# m20048_GPS.net
KiCad netlist of a schematic drawn in Altium Designer
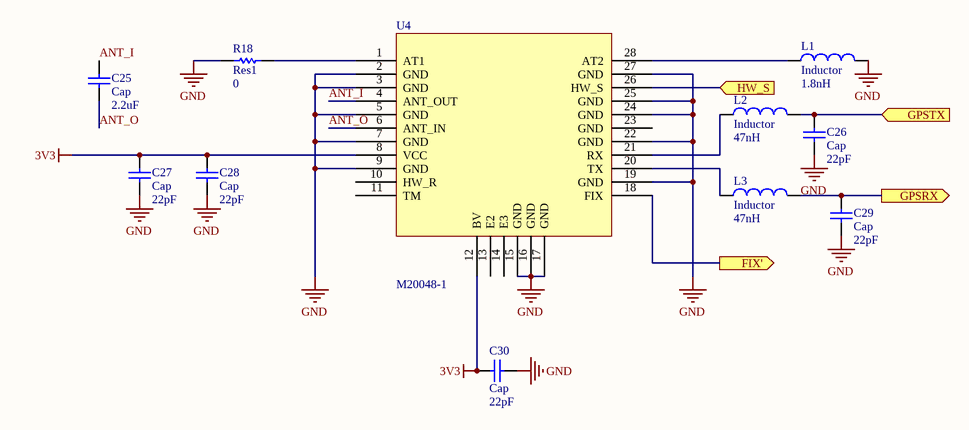
[diagram p0: m20048 GPS.SchDoc]

(export (version "E")
  (design (tool "Eeschema 10.0.6"))
  (components
    (comp (ref "C25")
      (value "Cap")
      (footprint "1608[0603]")
      (description "Capacitor")
      (fields (field (name "ALTIUM_VALUE") "2.2uF") (field (name "PUBLISHER") "Altium Limited"))
      (libsource (lib "Miscellaneous Devices") (part "Cap"))
    )
    (comp (ref "C26")
      (value "Cap")
      (footprint "0402-A")
      (description "Capacitor")
      (fields (field (name "ALTIUM_VALUE") "22pF") (field (name "PUBLISHER") "Altium Limited"))
      (libsource (lib "Miscellaneous Devices") (part "Cap"))
    )
    (comp (ref "C27")
      (value "Cap")
      (footprint "0402-A")
      (description "Capacitor")
      (fields (field (name "ALTIUM_VALUE") "22pF") (field (name "PUBLISHER") "Altium Limited"))
      (libsource (lib "Miscellaneous Devices") (part "Cap"))
    )
    (comp (ref "C28")
      (value "Cap")
      (footprint "0402-A")
      (description "Capacitor")
      (fields (field (name "ALTIUM_VALUE") "22pF") (field (name "PUBLISHER") "Altium Limited"))
      (libsource (lib "Miscellaneous Devices") (part "Cap"))
    )
    (comp (ref "C29")
      (value "Cap")
      (footprint "0402-A")
      (description "Capacitor")
      (fields (field (name "ALTIUM_VALUE") "22pF") (field (name "PUBLISHER") "Altium Limited"))
      (libsource (lib "Miscellaneous Devices") (part "Cap"))
    )
    (comp (ref "C30")
      (value "Cap")
      (footprint "0402-A")
      (description "Capacitor")
      (fields (field (name "ALTIUM_VALUE") "22pF") (field (name "PUBLISHER") "Altium Limited"))
      (libsource (lib "Miscellaneous Devices") (part "Cap"))
    )
    (comp (ref "L1")
      (value "Inductor")
      (footprint "0402-A")
      (fields (field (name "ALTIUM_VALUE") "1.8nH") (field (name "PUBLISHER") "Altium Limited"))
      (libsource (lib "Miscellaneous Devices") (part "Inductor"))
    )
    (comp (ref "L2")
      (value "Inductor")
      (footprint "0402-A")
      (fields (field (name "ALTIUM_VALUE") "47nH") (field (name "PUBLISHER") "Altium Limited"))
      (libsource (lib "Miscellaneous Devices") (part "Inductor"))
    )
    (comp (ref "L3")
      (value "Inductor")
      (footprint "0402-A")
      (fields (field (name "ALTIUM_VALUE") "47nH") (field (name "PUBLISHER") "Altium Limited"))
      (libsource (lib "Miscellaneous Devices") (part "Inductor"))
    )
    (comp (ref "R18")
      (value "Res1")
      (footprint "0402-A")
      (description "Resistor")
      (fields (field (name "ALTIUM_VALUE") "0") (field (name "PUBLISHER") "Altium Limited"))
      (libsource (lib "Miscellaneous Devices") (part "Res1"))
    )
    (comp (ref "U4") (value "M20048-1") (footprint "M20048-1") (libsource (lib "m20048") (part "M20048-1")))
  )
  (nets
    (net (code "1") (name "/ANT_I") (class "Default")
      (node (ref "C25") (pin "2") (pinfunction "2_2") (pintype "passive"))
      (node (ref "U4") (pin "4") (pinfunction "ANT_OUT_4") (pintype "passive"))
    )
    (net (code "2") (name "/ANT_O") (class "Default")
      (node (ref "C25") (pin "1") (pinfunction "1_1") (pintype "passive"))
      (node (ref "U4") (pin "6") (pinfunction "ANT_IN_6") (pintype "passive"))
    )
    (net (code "3") (name "/FIX'") (class "Default")
      (node (ref "U4") (pin "18") (pinfunction "FIX_18") (pintype "passive"))
    )
    (net (code "4") (name "/GPSRX") (class "Default")
      (node (ref "C29") (pin "2") (pinfunction "2_2") (pintype "passive"))
      (node (ref "L3") (pin "2") (pinfunction "2_2") (pintype "passive"))
    )
    (net (code "5") (name "/GPSTX") (class "Default")
      (node (ref "C26") (pin "2") (pinfunction "2_2") (pintype "passive"))
      (node (ref "L2") (pin "2") (pinfunction "2_2") (pintype "passive"))
    )
    (net (code "6") (name "/HW_S") (class "Default")
      (node (ref "U4") (pin "26") (pinfunction "HW_S_26") (pintype "passive"))
    )
    (net (code "7") (name "3V3") (class "Default")
      (node (ref "C27") (pin "2") (pinfunction "2_2") (pintype "passive"))
      (node (ref "C28") (pin "2") (pinfunction "2_2") (pintype "passive"))
      (node (ref "C30") (pin "2") (pinfunction "2_2") (pintype "passive"))
      (node (ref "U4") (pin "12") (pinfunction "BV_12") (pintype "passive"))
      (node (ref "U4") (pin "8") (pinfunction "VCC_8") (pintype "passive"))
    )
    (net (code "8") (name "GND") (class "Default")
      (node (ref "C26") (pin "1") (pinfunction "1_1") (pintype "passive"))
      (node (ref "C27") (pin "1") (pinfunction "1_1") (pintype "passive"))
      (node (ref "C28") (pin "1") (pinfunction "1_1") (pintype "passive"))
      (node (ref "C29") (pin "1") (pinfunction "1_1") (pintype "passive"))
      (node (ref "C30") (pin "1") (pinfunction "1_1") (pintype "passive"))
      (node (ref "L1") (pin "2") (pinfunction "2_2") (pintype "passive"))
      (node (ref "R18") (pin "1") (pinfunction "1_1") (pintype "passive"))
      (node (ref "U4") (pin "15") (pinfunction "GND_15") (pintype "passive"))
      (node (ref "U4") (pin "16") (pinfunction "GND_16") (pintype "passive"))
      (node (ref "U4") (pin "17") (pinfunction "GND_17") (pintype "passive"))
      (node (ref "U4") (pin "19") (pinfunction "GND_19") (pintype "passive"))
      (node (ref "U4") (pin "2") (pinfunction "GND_2") (pintype "passive"))
      (node (ref "U4") (pin "22") (pinfunction "GND_22") (pintype "passive"))
      (node (ref "U4") (pin "24") (pinfunction "GND_24") (pintype "passive"))
      (node (ref "U4") (pin "25") (pinfunction "GND_25") (pintype "passive"))
      (node (ref "U4") (pin "27") (pinfunction "GND_27") (pintype "passive"))
      (node (ref "U4") (pin "3") (pinfunction "GND_3") (pintype "passive"))
      (node (ref "U4") (pin "5") (pinfunction "GND_5") (pintype "passive"))
      (node (ref "U4") (pin "7") (pinfunction "GND_7") (pintype "passive"))
      (node (ref "U4") (pin "9") (pinfunction "GND_9") (pintype "passive"))
    )
    (net (code "9") (name "Net-(U4-AT1)") (class "Default")
      (node (ref "R18") (pin "2") (pinfunction "2_2") (pintype "passive"))
      (node (ref "U4") (pin "1") (pinfunction "AT1_1") (pintype "passive"))
    )
    (net (code "10") (name "Net-(U4-AT2)") (class "Default")
      (node (ref "L1") (pin "1") (pinfunction "1_1") (pintype "passive"))
      (node (ref "U4") (pin "28") (pinfunction "AT2_28") (pintype "passive"))
    )
    (net (code "11") (name "Net-(U4-RX)") (class "Default")
      (node (ref "L2") (pin "1") (pinfunction "1_1") (pintype "passive"))
      (node (ref "U4") (pin "21") (pinfunction "RX_21") (pintype "passive"))
    )
    (net (code "12") (name "Net-(U4-TX)") (class "Default")
      (node (ref "L3") (pin "1") (pinfunction "1_1") (pintype "passive"))
      (node (ref "U4") (pin "20") (pinfunction "TX_20") (pintype "passive"))
    )
    (net (code "13") (name "unconnected-(U4-E2-Pad13)") (class "Default")
      (node (ref "U4") (pin "13") (pinfunction "E2_13") (pintype "passive"))
    )
    (net (code "14") (name "unconnected-(U4-E3-Pad14)") (class "Default")
      (node (ref "U4") (pin "14") (pinfunction "E3_14") (pintype "passive"))
    )
    (net (code "15") (name "unconnected-(U4-GND-Pad23)") (class "Default")
      (node (ref "U4") (pin "23") (pinfunction "GND_23") (pintype "passive"))
    )
    (net (code "16") (name "unconnected-(U4-HW_R-Pad10)") (class "Default")
      (node (ref "U4") (pin "10") (pinfunction "HW_R_10") (pintype "passive"))
    )
    (net (code "17") (name "unconnected-(U4-TM-Pad11)") (class "Default")
      (node (ref "U4") (pin "11") (pinfunction "TM_11") (pintype "passive"))
    )
  )
)
